# ProProject_cload_F411_2motor_2spi_sensor.net
KiCad netlist of a schematic drawn in EasyEDA Pro
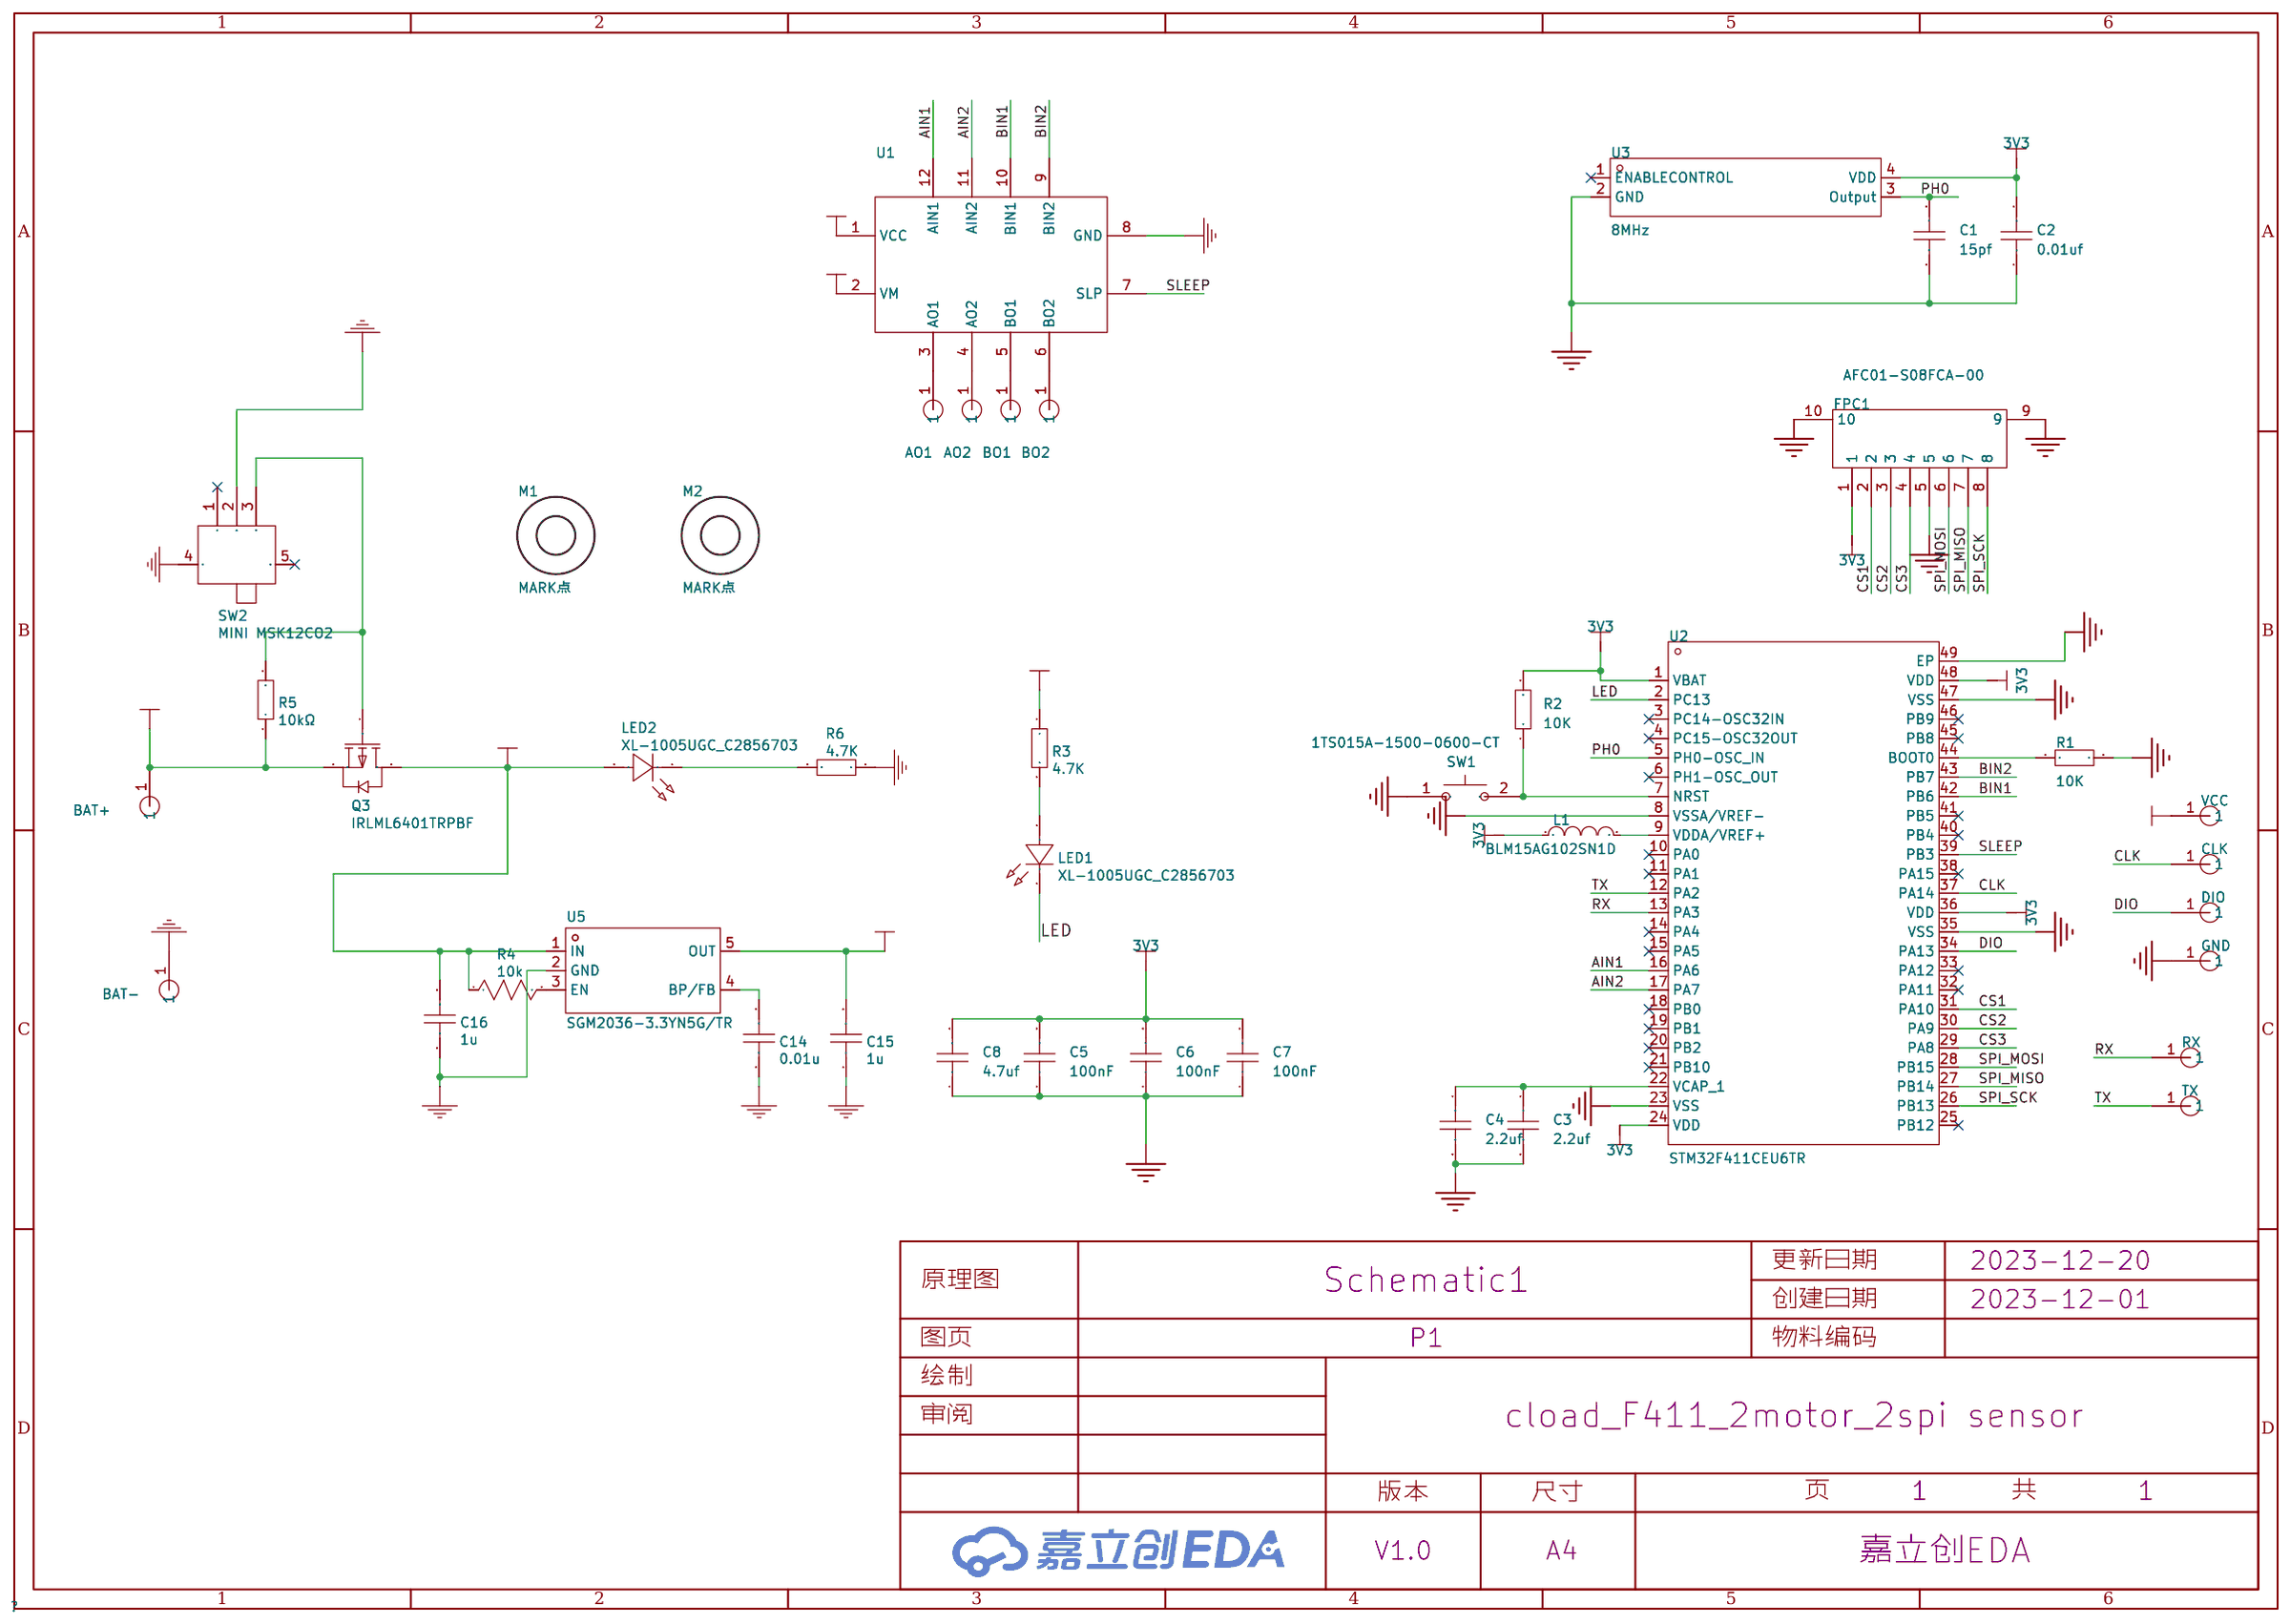
[diagram p0: schematic sheet]

(export (version "E")
  (design (tool "Eeschema 10.0.6"))
  (components
    (comp (ref "AO1")
      (value "TESTPOINT_D1.5mm")
      (footprint "easyedapro:TESTPOINT_D1.5MM")
      (libsource (lib "easyedapro") (part "TESTPOINT_D1.5mm"))
    )
    (comp (ref "AO2")
      (value "TESTPOINT_D1.5mm")
      (footprint "easyedapro:TESTPOINT_D1.5MM")
      (libsource (lib "easyedapro") (part "TESTPOINT_D1.5mm"))
    )
    (comp (ref "BAT+")
      (value "TESTPOINT_D1.5mm")
      (footprint "easyedapro:TESTPOINT_D1.5MM")
      (libsource (lib "easyedapro") (part "TESTPOINT_D1.5mm"))
    )
    (comp (ref "BAT-")
      (value "TESTPOINT_D1.5mm")
      (footprint "easyedapro:TESTPOINT_D1.5MM")
      (libsource (lib "easyedapro") (part "TESTPOINT_D1.5mm"))
    )
    (comp (ref "BO1")
      (value "TESTPOINT_D1.5mm")
      (footprint "easyedapro:TESTPOINT_D1.5MM")
      (libsource (lib "easyedapro") (part "TESTPOINT_D1.5mm"))
    )
    (comp (ref "BO2")
      (value "TESTPOINT_D1.5mm")
      (footprint "easyedapro:TESTPOINT_D1.5MM")
      (libsource (lib "easyedapro") (part "TESTPOINT_D1.5mm"))
    )
    (comp (ref "C1")
      (value "15pf")
      (footprint "easyedapro:C0402")
      (libsource (lib "easyedapro") (part "CapAcitance"))
    )
    (comp (ref "C2")
      (value "0.01uf")
      (footprint "easyedapro:C0402")
      (libsource (lib "easyedapro") (part "CapAcitance"))
    )
    (comp (ref "C3")
      (value "2.2uf")
      (footprint "easyedapro:C0402")
      (libsource (lib "easyedapro") (part "CapAcitance"))
    )
    (comp (ref "C4")
      (value "2.2uf")
      (footprint "easyedapro:C0402")
      (libsource (lib "easyedapro") (part "CapAcitance"))
    )
    (comp (ref "C5")
      (value "100nF")
      (footprint "easyedapro:C0402")
      (libsource (lib "easyedapro") (part "CapAcitance"))
    )
    (comp (ref "C6")
      (value "100nF")
      (footprint "easyedapro:C0402")
      (libsource (lib "easyedapro") (part "CapAcitance"))
    )
    (comp (ref "C7")
      (value "100nF")
      (footprint "easyedapro:C0402")
      (libsource (lib "easyedapro") (part "CapAcitance"))
    )
    (comp (ref "C8")
      (value "4.7uf")
      (footprint "easyedapro:C0402")
      (libsource (lib "easyedapro") (part "CapAcitance"))
    )
    (comp (ref "C14")
      (value "0.01u")
      (footprint "easyedapro:C0402")
      (libsource (lib "easyedapro") (part "0.01u"))
    )
    (comp (ref "C15") (value "1u") (footprint "easyedapro:C0402") (libsource (lib "easyedapro") (part "1u")))
    (comp (ref "C16") (value "1u") (footprint "easyedapro:C0402") (libsource (lib "easyedapro") (part "1u")))
    (comp (ref "CLK")
      (value "TESTPOINT_D1.5mm")
      (footprint "easyedapro:TESTPOINT_D1.5MM")
      (libsource (lib "easyedapro") (part "TESTPOINT_D1.5mm"))
    )
    (comp (ref "DIO")
      (value "TESTPOINT_D1.5mm")
      (footprint "easyedapro:TESTPOINT_D1.5MM")
      (libsource (lib "easyedapro") (part "TESTPOINT_D1.5mm"))
    )
    (comp (ref "FPC1")
      (value "AFC01-S08FCA-00")
      (footprint "easyedapro:FPC-SMD_P0.50-8P_FGS-XJ-H2.0")
      (description "间距:0.5mm;触点数量:8P;锁定特性:翻盖式;触点类型:下接;安装类型:卧贴;")
      (fields (field (name "Manufacturer") "JS(钜硕电子)"))
      (libsource (lib "easyedapro") (part "AFC01-S08FCA-00"))
    )
    (comp (ref "GND")
      (value "TESTPOINT_D1.5mm")
      (footprint "easyedapro:TESTPOINT_D1.5MM")
      (libsource (lib "easyedapro") (part "TESTPOINT_D1.5mm"))
    )
    (comp (ref "L1")
      (value "BLM15AG102SN1D")
      (footprint "easyedapro:L0402")
      (description "标称阻抗@测试频率:1kΩ@100MHz;误差:±25%;直流电阻(RDC):650mΩ;")
      (fields (field (name "Manufacturer") "muRata(村田)"))
      (libsource (lib "easyedapro") (part "BLM15AG102SN1D"))
    )
    (comp (ref "LED1")
      (value "XL-1005UGC_C2856703")
      (footprint "easyedapro:LED0402-RD_GREEN")
      (fields (field (name "Manufacturer Part") "XL-1005UGC") (field (name "Manufacturer") "XINGLIGHT(成兴光)"))
      (libsource (lib "easyedapro") (part "XL-1005UGC_C2856703"))
    )
    (comp (ref "LED2")
      (value "XL-1005UGC_C2856703")
      (footprint "easyedapro:LED0402-RD_GREEN")
      (fields (field (name "Manufacturer Part") "XL-1005UGC") (field (name "Manufacturer") "XINGLIGHT(成兴光)"))
      (libsource (lib "easyedapro") (part "XL-1005UGC_C2856703"))
    )
    (comp (ref "M1")
      (value "MARK点")
      (footprint "easyedapro:MARK点")
      (libsource (lib "easyedapro") (part "MARK点"))
    )
    (comp (ref "M2")
      (value "MARK点")
      (footprint "easyedapro:MARK点")
      (libsource (lib "easyedapro") (part "MARK点"))
    )
    (comp (ref "Q3")
      (value "IRLML6401TRPBF")
      (footprint "easyedapro:SOT-23-3_L2.9-W1.3-P1.90-LS2.4-BR")
      (fields (field (name "Manufacturer") "Infineon(英飞凌)"))
      (libsource (lib "easyedapro") (part "IRLML6401TRPBF"))
    )
    (comp (ref "R1") (value "10K") (footprint "easyedapro:R0402") (libsource (lib "easyedapro") (part "电阻")))
    (comp (ref "R2") (value "10K") (footprint "easyedapro:R0402") (libsource (lib "easyedapro") (part "电阻")))
    (comp (ref "R3")
      (value "4.7K")
      (footprint "easyedapro:R0402")
      (fields (field (name "Manufacturer Part") "RC0402FR-0710KL") (field (name "Manufacturer") "YAGEO(国巨)"))
      (libsource (lib "easyedapro") (part "4.7K"))
    )
    (comp (ref "R4") (value "10k") (footprint "easyedapro:R0402") (libsource (lib "easyedapro") (part "10k")))
    (comp (ref "R5")
      (value "10kΩ")
      (footprint "easyedapro:R0402")
      (fields (field (name "Manufacturer Part") "RC0402FR-0710KL") (field (name "Manufacturer") "YAGEO(国巨)"))
      (libsource (lib "easyedapro") (part "10kΩ"))
    )
    (comp (ref "R6")
      (value "4.7K")
      (footprint "easyedapro:R0402")
      (fields (field (name "Manufacturer Part") "RC0402FR-0710KL") (field (name "Manufacturer") "YAGEO(国巨)"))
      (libsource (lib "easyedapro") (part "4.7K"))
    )
    (comp (ref "RX")
      (value "TESTPOINT_D1.5mm")
      (footprint "easyedapro:TESTPOINT_D1.5MM")
      (libsource (lib "easyedapro") (part "TESTPOINT_D1.5mm"))
    )
    (comp (ref "SW1")
      (value "1TS015A-1500-0600-CT")
      (footprint "easyedapro:SW-SMD_L3.0-W2.0-LS3.5")
      (fields (field (name "Manufacturer") "HYP(鸿源精密)"))
      (libsource (lib "easyedapro") (part "1TS015A-1500-0600-CT"))
    )
    (comp (ref "SW2")
      (value "MINI MSK12CO2")
      (footprint "easyedapro:SW-SMD_MSK12CO2")
      (fields (field (name "Manufacturer") "SHOU HAN(首韩)"))
      (libsource (lib "easyedapro") (part "MINI MSK12CO2"))
    )
    (comp (ref "TX")
      (value "TESTPOINT_D1.5mm")
      (footprint "easyedapro:TESTPOINT_D1.5MM")
      (libsource (lib "easyedapro") (part "TESTPOINT_D1.5mm"))
    )
    (comp (ref "U1")
      (value "~")
      (footprint "easyedapro:DOUBLE_DRV8210")
      (libsource (lib "easyedapro") (part "DOUBLE_DRV8210"))
    )
    (comp (ref "U2")
      (value "STM32F411CEU6TR")
      (footprint "easyedapro:UFQFPN-48_L7.0-W7.0-P0.50-BL-EP5.6")
      (fields (field (name "Manufacturer") "ST(意法半导体)"))
      (libsource (lib "easyedapro") (part "STM32F411CEU6TR"))
    )
    (comp (ref "U3")
      (value "8MHz")
      (footprint "easyedapro:OSC-SMD_4P-L2.0-W1.6-BL")
      (description "频率:8MHz;工作电压:1.62V~3.63V;输出模式:CMOS;频率稳定度:±10ppm;")
      (fields
        (field (name "Manufacturer Part") "SX1M8.000M10F30TNN")
        (field (name "Manufacturer") "SCTF(星通时频)")
      )
      (libsource (lib "easyedapro") (part "SX1M8.000M10F30TNN"))
    )
    (comp (ref "U5")
      (value "SGM2036-3.3YN5G/TR")
      (footprint "easyedapro:SOT-23-5_L3.0-W1.7-P0.95-LS2.8-BR")
      (description "输出类型:固定;输出极性:正;输出通道数:1;最大输入电压:5.5V;输出电压:3.3V;压差:250mV@(300mA);输出电流:300mA;电源纹波抑制比(PSRR):82dB;")
      (fields (field (name "Manufacturer") "SGMICRO(圣邦微)"))
      (libsource (lib "easyedapro") (part "SGM2036-3.3YN5G/TR"))
    )
    (comp (ref "VCC")
      (value "TESTPOINT_D1.5mm")
      (footprint "easyedapro:TESTPOINT_D1.5MM")
      (libsource (lib "easyedapro") (part "TESTPOINT_D1.5mm"))
    )
  )
  (nets
    (net (code "1") (name "/AIN1") (class "Default")
      (node (ref "U1") (pin "12") (pinfunction "AIN1_12") (pintype "input"))
      (node (ref "U2") (pin "16") (pinfunction "PA6_16") (pintype "input"))
    )
    (net (code "2") (name "/AIN2") (class "Default")
      (node (ref "U1") (pin "11") (pinfunction "AIN2_11") (pintype "input"))
      (node (ref "U2") (pin "17") (pinfunction "PA7_17") (pintype "input"))
    )
    (net (code "3") (name "/BIN1") (class "Default")
      (node (ref "U1") (pin "10") (pinfunction "BIN1_10") (pintype "input"))
      (node (ref "U2") (pin "42") (pinfunction "PB6_42") (pintype "input"))
    )
    (net (code "4") (name "/BIN2") (class "Default")
      (node (ref "U1") (pin "9") (pinfunction "BIN2_9") (pintype "input"))
      (node (ref "U2") (pin "43") (pinfunction "PB7_43") (pintype "input"))
    )
    (net (code "5") (name "/CLK") (class "Default")
      (node (ref "CLK") (pin "1") (pinfunction "1_1") (pintype "unspecified"))
      (node (ref "U2") (pin "37") (pinfunction "PA14_37") (pintype "input"))
    )
    (net (code "6") (name "/CS1") (class "Default")
      (node (ref "FPC1") (pin "2") (pinfunction "2_2") (pintype "unspecified"))
      (node (ref "U2") (pin "31") (pinfunction "PA10_31") (pintype "input"))
    )
    (net (code "7") (name "/CS2") (class "Default")
      (node (ref "FPC1") (pin "3") (pinfunction "3_3") (pintype "unspecified"))
      (node (ref "U2") (pin "30") (pinfunction "PA9_30") (pintype "input"))
    )
    (net (code "8") (name "/CS3") (class "Default")
      (node (ref "FPC1") (pin "4") (pinfunction "4_4") (pintype "unspecified"))
      (node (ref "U2") (pin "29") (pinfunction "PA8_29") (pintype "input"))
    )
    (net (code "9") (name "/DIO") (class "Default")
      (node (ref "DIO") (pin "1") (pinfunction "1_1") (pintype "unspecified"))
      (node (ref "U2") (pin "34") (pinfunction "PA13_34") (pintype "input"))
    )
    (net (code "10") (name "/LED") (class "Default")
      (node (ref "LED1") (pin "1") (pinfunction "K_1") (pintype "unspecified"))
      (node (ref "U2") (pin "2") (pinfunction "PC13_2") (pintype "input"))
    )
    (net (code "11") (name "/PH0") (class "Default")
      (node (ref "C1") (pin "2") (pinfunction "2_2") (pintype "input"))
      (node (ref "U2") (pin "5") (pinfunction "PH0-OSC_IN_5") (pintype "input"))
      (node (ref "U3") (pin "3") (pinfunction "Output_3") (pintype "unspecified"))
    )
    (net (code "12") (name "/RX") (class "Default")
      (node (ref "RX") (pin "1") (pinfunction "1_1") (pintype "unspecified"))
      (node (ref "U2") (pin "13") (pinfunction "PA3_13") (pintype "input"))
    )
    (net (code "13") (name "/SLEEP") (class "Default")
      (node (ref "U1") (pin "7") (pinfunction "SLP_7") (pintype "input"))
      (node (ref "U2") (pin "39") (pinfunction "PB3_39") (pintype "input"))
    )
    (net (code "14") (name "/SPI_MISO") (class "Default")
      (node (ref "FPC1") (pin "7") (pinfunction "7_7") (pintype "unspecified"))
      (node (ref "U2") (pin "27") (pinfunction "PB14_27") (pintype "input"))
    )
    (net (code "15") (name "/SPI_MOSI") (class "Default")
      (node (ref "FPC1") (pin "6") (pinfunction "6_6") (pintype "unspecified"))
      (node (ref "U2") (pin "28") (pinfunction "PB15_28") (pintype "input"))
    )
    (net (code "16") (name "/SPI_SCK") (class "Default")
      (node (ref "FPC1") (pin "8") (pinfunction "8_8") (pintype "unspecified"))
      (node (ref "U2") (pin "26") (pinfunction "PB13_26") (pintype "input"))
    )
    (net (code "17") (name "/TX") (class "Default")
      (node (ref "TX") (pin "1") (pinfunction "1_1") (pintype "unspecified"))
      (node (ref "U2") (pin "12") (pinfunction "PA2_12") (pintype "input"))
    )
    (net (code "18") (name "3V3") (class "Default")
      (node (ref "C15") (pin "2") (pinfunction "2_2") (pintype "unspecified"))
      (node (ref "C2") (pin "2") (pinfunction "2_2") (pintype "input"))
      (node (ref "C5") (pin "2") (pinfunction "2_2") (pintype "input"))
      (node (ref "C6") (pin "2") (pinfunction "2_2") (pintype "input"))
      (node (ref "C7") (pin "2") (pinfunction "2_2") (pintype "input"))
      (node (ref "C8") (pin "2") (pinfunction "2_2") (pintype "input"))
      (node (ref "FPC1") (pin "1") (pinfunction "1_1") (pintype "unspecified"))
      (node (ref "L1") (pin "1") (pinfunction "1_1") (pintype "input"))
      (node (ref "R2") (pin "2") (pinfunction "2_2") (pintype "input"))
      (node (ref "R3") (pin "1") (pinfunction "1_1") (pintype "input"))
      (node (ref "U1") (pin "1") (pinfunction "VCC_1") (pintype "input"))
      (node (ref "U2") (pin "1") (pinfunction "VBAT_1") (pintype "input"))
      (node (ref "U2") (pin "24") (pinfunction "VDD_24") (pintype "input"))
      (node (ref "U2") (pin "36") (pinfunction "VDD_36") (pintype "input"))
      (node (ref "U2") (pin "48") (pinfunction "VDD_48") (pintype "input"))
      (node (ref "U3") (pin "4") (pinfunction "VDD_4") (pintype "unspecified"))
      (node (ref "U5") (pin "5") (pinfunction "OUT_5") (pintype "input"))
    )
    (net (code "19") (name "GND") (class "Default")
      (node (ref "BAT-") (pin "1") (pinfunction "1_1") (pintype "unspecified"))
      (node (ref "C1") (pin "1") (pinfunction "1_1") (pintype "input"))
      (node (ref "C14") (pin "1") (pinfunction "1_1") (pintype "unspecified"))
      (node (ref "C15") (pin "1") (pinfunction "1_1") (pintype "unspecified"))
      (node (ref "C16") (pin "1") (pinfunction "1_1") (pintype "unspecified"))
      (node (ref "C2") (pin "1") (pinfunction "1_1") (pintype "input"))
      (node (ref "C3") (pin "2") (pinfunction "2_2") (pintype "input"))
      (node (ref "C4") (pin "2") (pinfunction "2_2") (pintype "input"))
      (node (ref "C5") (pin "1") (pinfunction "1_1") (pintype "input"))
      (node (ref "C6") (pin "1") (pinfunction "1_1") (pintype "input"))
      (node (ref "C7") (pin "1") (pinfunction "1_1") (pintype "input"))
      (node (ref "C8") (pin "1") (pinfunction "1_1") (pintype "input"))
      (node (ref "FPC1") (pin "10") (pinfunction "10_10") (pintype "unspecified"))
      (node (ref "FPC1") (pin "5") (pinfunction "5_5") (pintype "unspecified"))
      (node (ref "FPC1") (pin "9") (pinfunction "9_9") (pintype "unspecified"))
      (node (ref "GND") (pin "1") (pinfunction "1_1") (pintype "unspecified"))
      (node (ref "R1") (pin "2") (pinfunction "2_2") (pintype "input"))
      (node (ref "R6") (pin "1") (pinfunction "1_1") (pintype "input"))
      (node (ref "SW1") (pin "1") (pinfunction "1_1") (pintype "input"))
      (node (ref "SW2") (pin "2") (pinfunction "2_2") (pintype "unspecified"))
      (node (ref "SW2") (pin "4") (pinfunction "4_4") (pintype "unspecified"))
      (node (ref "U1") (pin "8") (pinfunction "GND_8") (pintype "input"))
      (node (ref "U2") (pin "23") (pinfunction "VSS_23") (pintype "input"))
      (node (ref "U2") (pin "35") (pinfunction "VSS_35") (pintype "input"))
      (node (ref "U2") (pin "47") (pinfunction "VSS_47") (pintype "input"))
      (node (ref "U2") (pin "49") (pinfunction "EP_49") (pintype "input"))
      (node (ref "U2") (pin "8") (pinfunction "VSSA/VREF-_8") (pintype "input"))
      (node (ref "U3") (pin "2") (pinfunction "GND_2") (pintype "unspecified"))
      (node (ref "U5") (pin "2") (pinfunction "GND_2") (pintype "input"))
    )
    (net (code "20") (name "Net-(LED1-A)") (class "Default")
      (node (ref "LED1") (pin "2") (pinfunction "A_2") (pintype "unspecified"))
      (node (ref "R3") (pin "2") (pinfunction "2_2") (pintype "input"))
    )
    (net (code "21") (name "Net-(LED2-K)") (class "Default")
      (node (ref "LED2") (pin "1") (pinfunction "K_1") (pintype "unspecified"))
      (node (ref "R6") (pin "2") (pinfunction "2_2") (pintype "input"))
    )
    (net (code "22") (name "Net-(Q3-G)") (class "Default")
      (node (ref "Q3") (pin "1") (pinfunction "G_1") (pintype "unspecified"))
      (node (ref "R5") (pin "2") (pinfunction "2_2") (pintype "input"))
      (node (ref "SW2") (pin "3") (pinfunction "3_3") (pintype "unspecified"))
    )
    (net (code "23") (name "Net-(U1-AO1)") (class "Default")
      (node (ref "AO1") (pin "1") (pinfunction "1_1") (pintype "unspecified"))
      (node (ref "U1") (pin "3") (pinfunction "AO1_3") (pintype "input"))
    )
    (net (code "24") (name "Net-(U1-AO2)") (class "Default")
      (node (ref "AO2") (pin "1") (pinfunction "1_1") (pintype "unspecified"))
      (node (ref "U1") (pin "4") (pinfunction "AO2_4") (pintype "input"))
    )
    (net (code "25") (name "Net-(U1-BO1)") (class "Default")
      (node (ref "BO1") (pin "1") (pinfunction "1_1") (pintype "unspecified"))
      (node (ref "U1") (pin "5") (pinfunction "BO1_5") (pintype "input"))
    )
    (net (code "26") (name "Net-(U1-BO2)") (class "Default")
      (node (ref "BO2") (pin "1") (pinfunction "1_1") (pintype "unspecified"))
      (node (ref "U1") (pin "6") (pinfunction "BO2_6") (pintype "input"))
    )
    (net (code "27") (name "Net-(U2-BOOT0)") (class "Default")
      (node (ref "R1") (pin "1") (pinfunction "1_1") (pintype "input"))
      (node (ref "U2") (pin "44") (pinfunction "BOOT0_44") (pintype "input"))
    )
    (net (code "28") (name "Net-(U2-NRST)") (class "Default")
      (node (ref "R2") (pin "1") (pinfunction "1_1") (pintype "input"))
      (node (ref "SW1") (pin "2") (pinfunction "2_2") (pintype "input"))
      (node (ref "U2") (pin "7") (pinfunction "NRST_7") (pintype "input"))
    )
    (net (code "29") (name "Net-(U2-VCAP_1)") (class "Default")
      (node (ref "C3") (pin "1") (pinfunction "1_1") (pintype "input"))
      (node (ref "C4") (pin "1") (pinfunction "1_1") (pintype "input"))
      (node (ref "U2") (pin "22") (pinfunction "VCAP_1_22") (pintype "input"))
    )
    (net (code "30") (name "Net-(U2-VDDA{slash}VREF+)") (class "Default")
      (node (ref "L1") (pin "2") (pinfunction "2_2") (pintype "input"))
      (node (ref "U2") (pin "9") (pinfunction "VDDA/VREF+_9") (pintype "input"))
    )
    (net (code "31") (name "Net-(U5-BP{slash}FB)") (class "Default")
      (node (ref "C14") (pin "2") (pinfunction "2_2") (pintype "unspecified"))
      (node (ref "U5") (pin "4") (pinfunction "BP/FB_4") (pintype "input"))
    )
    (net (code "32") (name "Net-(U5-EN)") (class "Default")
      (node (ref "R4") (pin "2") (pinfunction "2_2") (pintype "unspecified"))
      (node (ref "U5") (pin "3") (pinfunction "EN_3") (pintype "input"))
    )
    (net (code "33") (name "VBAT") (class "Default")
      (node (ref "BAT+") (pin "1") (pinfunction "1_1") (pintype "unspecified"))
      (node (ref "Q3") (pin "2") (pinfunction "S_2") (pintype "unspecified"))
      (node (ref "R5") (pin "1") (pinfunction "1_1") (pintype "input"))
    )
    (net (code "34") (name "VCC") (class "Default")
      (node (ref "C16") (pin "2") (pinfunction "2_2") (pintype "unspecified"))
      (node (ref "LED2") (pin "2") (pinfunction "A_2") (pintype "unspecified"))
      (node (ref "Q3") (pin "3") (pinfunction "D_3") (pintype "unspecified"))
      (node (ref "R4") (pin "1") (pinfunction "1_1") (pintype "unspecified"))
      (node (ref "U1") (pin "2") (pinfunction "VM_2") (pintype "input"))
      (node (ref "U5") (pin "1") (pinfunction "IN_1") (pintype "input"))
      (node (ref "VCC") (pin "1") (pinfunction "1_1") (pintype "unspecified"))
    )
    (net (code "35") (name "unconnected-(SW2-Pad1)") (class "Default")
      (node (ref "SW2") (pin "1") (pinfunction "1_1") (pintype "unspecified+no_connect"))
    )
    (net (code "36") (name "unconnected-(SW2-Pad5)") (class "Default")
      (node (ref "SW2") (pin "5") (pinfunction "5_5") (pintype "unspecified+no_connect"))
    )
    (net (code "37") (name "unconnected-(U2-PA0-Pad10)") (class "Default")
      (node (ref "U2") (pin "10") (pinfunction "PA0_10") (pintype "input+no_connect"))
    )
    (net (code "38") (name "unconnected-(U2-PA1-Pad11)") (class "Default")
      (node (ref "U2") (pin "11") (pinfunction "PA1_11") (pintype "input+no_connect"))
    )
    (net (code "39") (name "unconnected-(U2-PA4-Pad14)") (class "Default")
      (node (ref "U2") (pin "14") (pinfunction "PA4_14") (pintype "input+no_connect"))
    )
    (net (code "40") (name "unconnected-(U2-PA5-Pad15)") (class "Default")
      (node (ref "U2") (pin "15") (pinfunction "PA5_15") (pintype "input+no_connect"))
    )
    (net (code "41") (name "unconnected-(U2-PA11-Pad32)") (class "Default")
      (node (ref "U2") (pin "32") (pinfunction "PA11_32") (pintype "input+no_connect"))
    )
    (net (code "42") (name "unconnected-(U2-PA12-Pad33)") (class "Default")
      (node (ref "U2") (pin "33") (pinfunction "PA12_33") (pintype "input+no_connect"))
    )
    (net (code "43") (name "unconnected-(U2-PA15-Pad38)") (class "Default")
      (node (ref "U2") (pin "38") (pinfunction "PA15_38") (pintype "input+no_connect"))
    )
    (net (code "44") (name "unconnected-(U2-PB0-Pad18)") (class "Default")
      (node (ref "U2") (pin "18") (pinfunction "PB0_18") (pintype "input+no_connect"))
    )
    (net (code "45") (name "unconnected-(U2-PB1-Pad19)") (class "Default")
      (node (ref "U2") (pin "19") (pinfunction "PB1_19") (pintype "input+no_connect"))
    )
    (net (code "46") (name "unconnected-(U2-PB2-Pad20)") (class "Default")
      (node (ref "U2") (pin "20") (pinfunction "PB2_20") (pintype "input+no_connect"))
    )
    (net (code "47") (name "unconnected-(U2-PB4-Pad40)") (class "Default")
      (node (ref "U2") (pin "40") (pinfunction "PB4_40") (pintype "input+no_connect"))
    )
    (net (code "48") (name "unconnected-(U2-PB5-Pad41)") (class "Default")
      (node (ref "U2") (pin "41") (pinfunction "PB5_41") (pintype "input+no_connect"))
    )
    (net (code "49") (name "unconnected-(U2-PB8-Pad45)") (class "Default")
      (node (ref "U2") (pin "45") (pinfunction "PB8_45") (pintype "input+no_connect"))
    )
    (net (code "50") (name "unconnected-(U2-PB9-Pad46)") (class "Default")
      (node (ref "U2") (pin "46") (pinfunction "PB9_46") (pintype "input+no_connect"))
    )
    (net (code "51") (name "unconnected-(U2-PB10-Pad21)") (class "Default")
      (node (ref "U2") (pin "21") (pinfunction "PB10_21") (pintype "input+no_connect"))
    )
    (net (code "52") (name "unconnected-(U2-PB12-Pad25)") (class "Default")
      (node (ref "U2") (pin "25") (pinfunction "PB12_25") (pintype "input+no_connect"))
    )
    (net (code "53") (name "unconnected-(U2-PC14-OSC32IN-Pad3)") (class "Default")
      (node (ref "U2") (pin "3") (pinfunction "PC14-OSC32IN_3") (pintype "input+no_connect"))
    )
    (net (code "54") (name "unconnected-(U2-PC15-OSC32OUT-Pad4)") (class "Default")
      (node (ref "U2") (pin "4") (pinfunction "PC15-OSC32OUT_4") (pintype "input+no_connect"))
    )
    (net (code "55") (name "unconnected-(U2-PH1-OSC_OUT-Pad6)") (class "Default")
      (node (ref "U2") (pin "6") (pinfunction "PH1-OSC_OUT_6") (pintype "input+no_connect"))
    )
    (net (code "56") (name "unconnected-(U3-ENABLECONTROL-Pad1)") (class "Default")
      (node (ref "U3") (pin "1") (pinfunction "ENABLECONTROL_1") (pintype "unspecified+no_connect"))
    )
  )
)
